# FIT_TCM_P3V3.net
KiCad netlist of a schematic drawn in Altium Designer
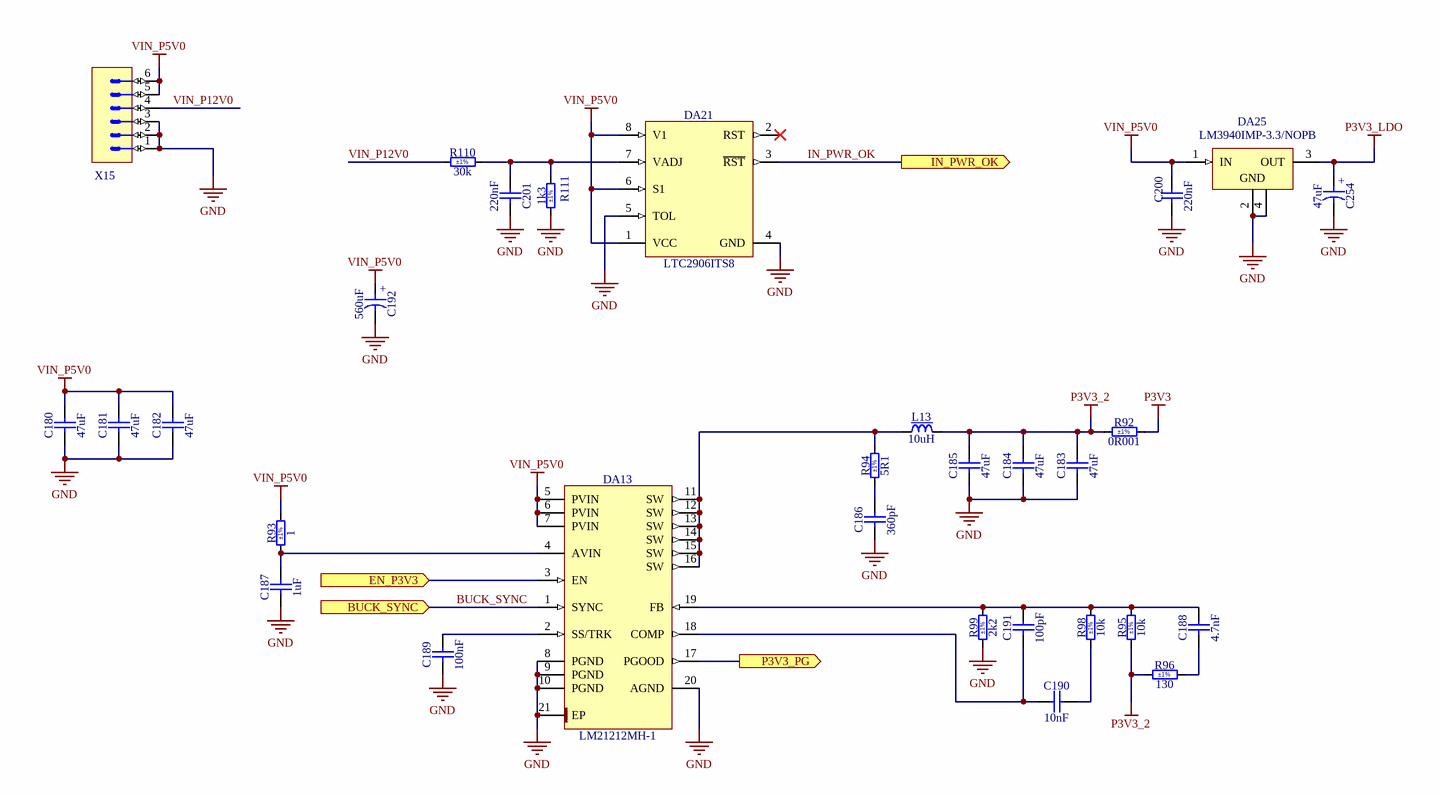
[diagram p0: FIT_TCM_P3V3.SchDoc]

(export (version "E")
  (design (tool "Eeschema 10.0.6"))
  (components
    (comp (ref "C180")
      (value "47uF")
      (footprint "CAPC3225X270N")
      (description "Non-polarised capacitor")
      (fields
        (field (name "PART NUMBER") "CC1210_47UF_16V_20%_X5R")
        (field (name "VOLTAGE") "16V")
        (field (name "AUTHOR") "CERN DEM MR")
      )
      (libsource (lib "Capacitors") (part "Capacitor - non polarized"))
    )
    (comp (ref "C181")
      (value "47uF")
      (footprint "CAPC3225X270N")
      (description "Non-polarised capacitor")
      (fields
        (field (name "PART NUMBER") "CC1210_47UF_16V_20%_X5R")
        (field (name "VOLTAGE") "16V")
        (field (name "AUTHOR") "CERN DEM MR")
      )
      (libsource (lib "Capacitors") (part "Capacitor - non polarized"))
    )
    (comp (ref "C182")
      (value "47uF")
      (footprint "CAPC3225X270N")
      (description "Non-polarised capacitor")
      (fields
        (field (name "PART NUMBER") "CC1210_47UF_16V_20%_X5R")
        (field (name "VOLTAGE") "16V")
        (field (name "AUTHOR") "CERN DEM MR")
      )
      (libsource (lib "Capacitors") (part "Capacitor - non polarized"))
    )
    (comp (ref "C183")
      (value "47uF")
      (footprint "CAPC3225X270N")
      (description "Non-polarised capacitor")
      (fields
        (field (name "PART NUMBER") "CC1210_47UF_16V_20%_X5R")
        (field (name "VOLTAGE") "16V")
        (field (name "AUTHOR") "CERN DEM MR")
      )
      (libsource (lib "Capacitors") (part "Capacitor - non polarized"))
    )
    (comp (ref "C184")
      (value "47uF")
      (footprint "CAPC3225X270N")
      (description "Non-polarised capacitor")
      (fields
        (field (name "PART NUMBER") "CC1210_47UF_16V_20%_X5R")
        (field (name "VOLTAGE") "16V")
        (field (name "AUTHOR") "CERN DEM MR")
      )
      (libsource (lib "Capacitors") (part "Capacitor - non polarized"))
    )
    (comp (ref "C185")
      (value "47uF")
      (footprint "CAPC3225X270N")
      (description "Non-polarised capacitor")
      (fields
        (field (name "PART NUMBER") "CC1210_47UF_16V_20%_X5R")
        (field (name "VOLTAGE") "16V")
        (field (name "AUTHOR") "CERN DEM MR")
      )
      (libsource (lib "Capacitors") (part "Capacitor - non polarized"))
    )
    (comp (ref "C186")
      (value "360pF")
      (footprint "CAPC2013X145N")
      (description "Non-polarised capacitor")
      (fields
        (field (name "PART NUMBER") "CC0805_360PF_50V_5%_C0G")
        (field (name "VOLTAGE") "50V")
        (field (name "AUTHOR") "CERN DEM HF")
      )
      (libsource (lib "Capacitors") (part "Capacitor - non polarized"))
    )
    (comp (ref "C187")
      (value "1uF")
      (footprint "CAPC2012X140N")
      (description "Non-polarised capacitor")
      (fields
        (field (name "PART NUMBER") "CC0805_1UF_25V_10%_X7R")
        (field (name "VOLTAGE") "25V")
        (field (name "AUTHOR") "CERN DEM JLC")
      )
      (libsource (lib "Capacitors") (part "Capacitor - non polarized"))
    )
    (comp (ref "C188")
      (value "4.7nF")
      (footprint "CAPC2012X95N")
      (description "Non-polarised capacitor")
      (fields
        (field (name "PART NUMBER") "CC0805_4.7NF_50V_5%_NP0")
        (field (name "VOLTAGE") "50V")
        (field (name "AUTHOR") "CERN DEM MR")
      )
      (libsource (lib "Capacitors") (part "Capacitor - non polarized"))
    )
    (comp (ref "C189")
      (value "100nF")
      (footprint "CAPC2012X135N")
      (description "Non-polarised capacitor")
      (fields
        (field (name "PART NUMBER") "CC0805_100NF_50V_10%_X7R")
        (field (name "VOLTAGE") "50V")
        (field (name "AUTHOR") "CERN DEM JLC")
      )
      (libsource (lib "Capacitors") (part "Capacitor - non polarized"))
    )
    (comp (ref "C190")
      (value "10nF")
      (footprint "CAPC2012X135N")
      (description "Non-polarised capacitor")
      (fields
        (field (name "PART NUMBER") "CC0805_10NF_50V_10%_X7R")
        (field (name "VOLTAGE") "50V")
        (field (name "AUTHOR") "CERN DEM JLC")
      )
      (libsource (lib "Capacitors") (part "Capacitor - non polarized"))
    )
    (comp (ref "C191")
      (value "100pF")
      (footprint "CAPC2012X135N")
      (description "Non-polarised capacitor")
      (fields
        (field (name "PART NUMBER") "CC0805_100PF_50V_5%_NP0")
        (field (name "VOLTAGE") "50V")
        (field (name "AUTHOR") "CERN DEM JLC")
      )
      (libsource (lib "Capacitors") (part "Capacitor - non polarized"))
    )
    (comp (ref "C192")
      (value "560uF")
      (footprint "CAPAE830X1020N")
      (description "Polarised capacitor")
      (fields
        (field (name "PART NUMBER") "CAE830-1020_560UF_10V_20%")
        (field (name "VOLTAGE") "10V")
        (field (name "AUTHOR") "CERN DEM HF")
      )
      (libsource (lib "Capacitors") (part "Capacitor - polarized"))
    )
    (comp (ref "C200")
      (value "220nF")
      (footprint "CAPC2012X135N")
      (description "Non-polarised capacitor")
      (fields
        (field (name "PART NUMBER") "CC0805_220NF_50V_10%_X7R")
        (field (name "VOLTAGE") "50V")
        (field (name "AUTHOR") "CERN DEM JLC")
      )
      (libsource (lib "Capacitors") (part "Capacitor - non polarized"))
    )
    (comp (ref "C201")
      (value "220nF")
      (footprint "CAPC2012X135N")
      (description "Non-polarised capacitor")
      (fields
        (field (name "PART NUMBER") "CC0805_220NF_50V_10%_X7R")
        (field (name "VOLTAGE") "50V")
        (field (name "AUTHOR") "CERN DEM JLC")
      )
      (libsource (lib "Capacitors") (part "Capacitor - non polarized"))
    )
    (comp (ref "C254")
      (value "47uF")
      (footprint "CAPAE530X610N")
      (description "Polarised capacitor")
      (fields
        (field (name "PART NUMBER") "CAE530-610_47UF_16V_20%")
        (field (name "VOLTAGE") "16V")
        (field (name "AUTHOR") "CERN DEM HF")
      )
      (libsource (lib "Capacitors") (part "Capacitor - polarized"))
    )
    (comp (ref "DA13")
      (value "LM21212MH-1")
      (footprint "TEXAS_PWP0020AA")
      (description "2.95-V To 5.5-V, 12-A, Voltage-Mode Synchronous Buck Regulator with Frequency Synchronization")
      (fields (field (name "MANUFACTURER") "TEXAS INSTRUMENTS") (field (name "AUTHOR") "CERN DEM HF"))
      (libsource (lib "ICs And Semiconductors") (part "LM21212"))
    )
    (comp (ref "DA21")
      (value "LTC2906ITS8")
      (footprint "SOT65P280X100-8N")
      (description "Precision Dual Supply Monitors with One Pin-Selectable Threshold and One Adjustable Input")
      (fields (field (name "MANUFACTURER") "LINEAR TECHNOLOGY") (field (name "AUTHOR") "CERN DEM HF"))
      (libsource (lib "ICs And Semiconductors") (part "LTC2906xTS8"))
    )
    (comp (ref "DA25")
      (value "LM3940IMP-3.3/NOPB")
      (footprint "SOT230P700X180-4N")
      (description "3-Terminal Regulator 1=IN 2=GND 3=OUT 4=GND")
      (fields
        (field (name "MANUFACTURER") "TEXAS INSTRUMENTS")
        (field (name "MANUFACTURER PART NUMBER") "LM3940IMP-3.3")
        (field (name "AUTHOR") "CERN DEM JLC")
      )
      (libsource (lib "ICs And Semiconductors") (part "REG3+1 1IN-2GND-3OUT+4GND"))
    )
    (comp (ref "L13")
      (value "10uH")
      (footprint "IND_VISHAY_IHPL4040DZ-01")
      (description "Inductor With Core")
      (fields
        (field (name "PART NUMBER") "IND4040_10UH_20%_VISHAY_IHLP-4040DZ-01")
        (field (name "POWER") "6.8A")
        (field (name "AUTHOR") "CERN DEM HF")
      )
      (libsource (lib "Inductors & Transformers") (part "Inductor With Magnetic core"))
    )
    (comp (ref "R92")
      (value "0R001")
      (footprint "RESC_BOURNS_CRE2512_0R001-0R004")
      (description "Resistor - 1%")
      (fields
        (field (name "TOLERANCE") "±1%")
        (field (name "PART NUMBER") "R2512_0R001_1%_3W_50PPM_BOURNS_CRE2512")
        (field (name "POWER") "3W")
        (field (name "AUTHOR") "CERN DEM BC")
      )
      (libsource (lib "Resistors") (part "Resistor - 1%"))
    )
    (comp (ref "R93")
      (value "1")
      (footprint "RESC2012X60N")
      (description "Resistor - 1%")
      (fields
        (field (name "TOLERANCE") "±1%")
        (field (name "PART NUMBER") "R0805_1R_1%_0.125W_100PPM")
        (field (name "POWER") "0.125W")
        (field (name "AUTHOR") "CERN DEM HF")
      )
      (libsource (lib "Resistors") (part "Resistor - 1%"))
    )
    (comp (ref "R94")
      (value "5R1")
      (footprint "RESC2012X60N")
      (description "Resistor - 1%")
      (fields
        (field (name "TOLERANCE") "±1%")
        (field (name "PART NUMBER") "R0805_5R1_1%_0.125W_100PPM")
        (field (name "POWER") "0.125W")
        (field (name "AUTHOR") "CERN DEM HF")
      )
      (libsource (lib "Resistors") (part "Resistor - 1%"))
    )
    (comp (ref "R95")
      (value "10k")
      (footprint "RESC2012X60N")
      (description "Resistor - 1%")
      (fields
        (field (name "TOLERANCE") "±1%")
        (field (name "PART NUMBER") "R0805_10K_1%_0.125W_100PPM")
        (field (name "POWER") "0.125W")
        (field (name "AUTHOR") "CERN DEM JLC")
      )
      (libsource (lib "Resistors") (part "Resistor - 1%"))
    )
    (comp (ref "R96")
      (value "130")
      (footprint "RESC2012X60N")
      (description "Resistor - 1%")
      (fields
        (field (name "TOLERANCE") "±1%")
        (field (name "PART NUMBER") "R0805_130R_1%_0.125W_100PPM")
        (field (name "POWER") "0.125W")
        (field (name "AUTHOR") "CERN DEM JLC")
      )
      (libsource (lib "Resistors") (part "Resistor - 1%"))
    )
    (comp (ref "R98")
      (value "10k")
      (footprint "RESC2012X60N")
      (description "Resistor - 1%")
      (fields
        (field (name "TOLERANCE") "±1%")
        (field (name "PART NUMBER") "R0805_10K_1%_0.125W_100PPM")
        (field (name "POWER") "0.125W")
        (field (name "AUTHOR") "CERN DEM JLC")
      )
      (libsource (lib "Resistors") (part "Resistor - 1%"))
    )
    (comp (ref "R99")
      (value "2k2")
      (footprint "RESC2012X60N")
      (description "Resistor - 1%")
      (fields
        (field (name "TOLERANCE") "±1%")
        (field (name "PART NUMBER") "R0805_2K2_1%_0.125W_100PPM")
        (field (name "POWER") "0.125W")
        (field (name "AUTHOR") "CERN DEM JLC")
      )
      (libsource (lib "Resistors") (part "Resistor - 1%"))
    )
    (comp (ref "R110")
      (value "30k")
      (footprint "RESC2012X60N")
      (description "Resistor - 1%")
      (fields
        (field (name "TOLERANCE") "±1%")
        (field (name "PART NUMBER") "R0805_30K_1%_0.125W_100PPM")
        (field (name "POWER") "0.125W")
        (field (name "AUTHOR") "CERN DEM JLC")
      )
      (libsource (lib "Resistors") (part "Resistor - 1%"))
    )
    (comp (ref "R111")
      (value "1k3")
      (footprint "RESC2012X60N")
      (description "Resistor - 1%")
      (fields
        (field (name "TOLERANCE") "±1%")
        (field (name "PART NUMBER") "R0805_1K3_1%_0.125W_100PPM")
        (field (name "POWER") "0.125W")
        (field (name "AUTHOR") "CERN DEM JLC")
      )
      (libsource (lib "Resistors") (part "Resistor - 1%"))
    )
    (comp (ref "X15")
      (value "Mini-Fit BMI")
      (footprint "MOLEX_15-24-9067")
      (description "Connector 6 Male")
      (fields
        (field (name "PART NUMBER") "MOLEX_15-24-9067")
        (field (name "MANUFACTURER") "MOLEX")
        (field (name "AUTHOR") "CERN DEM HF")
      )
      (libsource (lib "Connectors") (part "Connector 6 Male"))
    )
  )
  (nets
    (net (code "1") (name "/BUCK_SYNC") (class "Default")
      (node (ref "DA13") (pin "1") (pinfunction "SYNC_1") (pintype "input"))
    )
    (net (code "2") (name "/EN_P3V3") (class "Default")
      (node (ref "DA13") (pin "3") (pinfunction "EN_3") (pintype "input"))
    )
    (net (code "3") (name "/IN_PWR_OK") (class "Default")
      (node (ref "DA21") (pin "3") (pinfunction "~{RST}_3") (pintype "output"))
    )
    (net (code "4") (name "/P3V3_PG") (class "Default")
      (node (ref "DA13") (pin "17") (pinfunction "PGOOD_17") (pintype "output"))
    )
    (net (code "5") (name "/VIN_P12V0") (class "Default")
      (node (ref "R110") (pin "2") (pinfunction "2_2") (pintype "passive"))
      (node (ref "X15") (pin "4") (pinfunction "4_4") (pintype "bidirectional"))
    )
    (net (code "6") (name "GND") (class "Default")
      (node (ref "C180") (pin "1") (pinfunction "1_1") (pintype "passive"))
      (node (ref "C181") (pin "1") (pinfunction "1_1") (pintype "passive"))
      (node (ref "C182") (pin "1") (pinfunction "1_1") (pintype "passive"))
      (node (ref "C183") (pin "1") (pinfunction "1_1") (pintype "passive"))
      (node (ref "C184") (pin "1") (pinfunction "1_1") (pintype "passive"))
      (node (ref "C185") (pin "1") (pinfunction "1_1") (pintype "passive"))
      (node (ref "C186") (pin "1") (pinfunction "1_1") (pintype "passive"))
      (node (ref "C187") (pin "1") (pinfunction "1_1") (pintype "passive"))
      (node (ref "C189") (pin "1") (pinfunction "1_1") (pintype "passive"))
      (node (ref "C192") (pin "2") (pinfunction "2_2") (pintype "passive"))
      (node (ref "C200") (pin "1") (pinfunction "1_1") (pintype "passive"))
      (node (ref "C201") (pin "1") (pinfunction "1_1") (pintype "passive"))
      (node (ref "C254") (pin "2") (pinfunction "2_2") (pintype "passive"))
      (node (ref "DA13") (pin "10") (pinfunction "PGND_10") (pintype "power_in"))
      (node (ref "DA13") (pin "20") (pinfunction "AGND_20") (pintype "power_in"))
      (node (ref "DA13") (pin "21") (pinfunction "EP_21") (pintype "power_in"))
      (node (ref "DA13") (pin "8") (pinfunction "PGND_8") (pintype "power_in"))
      (node (ref "DA13") (pin "9") (pinfunction "PGND_9") (pintype "power_in"))
      (node (ref "DA21") (pin "4") (pinfunction "GND_4") (pintype "power_in"))
      (node (ref "DA21") (pin "5") (pinfunction "TOL_5") (pintype "input"))
      (node (ref "DA25") (pin "2") (pinfunction "GND_2") (pintype "power_in"))
      (node (ref "DA25") (pin "4") (pinfunction "GND_4") (pintype "power_in"))
      (node (ref "R111") (pin "1") (pinfunction "1_1") (pintype "passive"))
      (node (ref "R99") (pin "1") (pinfunction "1_1") (pintype "passive"))
      (node (ref "X15") (pin "1") (pinfunction "1_1") (pintype "bidirectional"))
      (node (ref "X15") (pin "2") (pinfunction "2_2") (pintype "bidirectional"))
      (node (ref "X15") (pin "3") (pinfunction "3_3") (pintype "bidirectional"))
    )
    (net (code "7") (name "Net-(C186-Pad2)") (class "Default")
      (node (ref "C186") (pin "2") (pinfunction "2_2") (pintype "passive"))
      (node (ref "R94") (pin "1") (pinfunction "1_1") (pintype "passive"))
    )
    (net (code "8") (name "Net-(C188-Pad1)") (class "Default")
      (node (ref "C188") (pin "1") (pinfunction "1_1") (pintype "passive"))
      (node (ref "R96") (pin "1") (pinfunction "1_1") (pintype "passive"))
    )
    (net (code "9") (name "Net-(C190-Pad1)") (class "Default")
      (node (ref "C190") (pin "1") (pinfunction "1_1") (pintype "passive"))
      (node (ref "R98") (pin "1") (pinfunction "1_1") (pintype "passive"))
    )
    (net (code "10") (name "Net-(DA13-AVIN)") (class "Default")
      (node (ref "C187") (pin "2") (pinfunction "2_2") (pintype "passive"))
      (node (ref "DA13") (pin "4") (pinfunction "AVIN_4") (pintype "power_in"))
      (node (ref "R93") (pin "1") (pinfunction "1_1") (pintype "passive"))
    )
    (net (code "11") (name "Net-(DA13-COMP)") (class "Default")
      (node (ref "C190") (pin "2") (pinfunction "2_2") (pintype "passive"))
      (node (ref "C191") (pin "1") (pinfunction "1_1") (pintype "passive"))
      (node (ref "DA13") (pin "18") (pinfunction "COMP_18") (pintype "output"))
    )
    (net (code "12") (name "Net-(DA13-FB)") (class "Default")
      (node (ref "C188") (pin "2") (pinfunction "2_2") (pintype "passive"))
      (node (ref "C191") (pin "2") (pinfunction "2_2") (pintype "passive"))
      (node (ref "DA13") (pin "19") (pinfunction "FB_19") (pintype "input"))
      (node (ref "R95") (pin "2") (pinfunction "2_2") (pintype "passive"))
      (node (ref "R98") (pin "2") (pinfunction "2_2") (pintype "passive"))
      (node (ref "R99") (pin "2") (pinfunction "2_2") (pintype "passive"))
    )
    (net (code "13") (name "Net-(DA13-SS{slash}TRK)") (class "Default")
      (node (ref "C189") (pin "2") (pinfunction "2_2") (pintype "passive"))
      (node (ref "DA13") (pin "2") (pinfunction "SS/TRK_2") (pintype "input"))
    )
    (net (code "14") (name "Net-(DA13-SW-Pad11)") (class "Default")
      (node (ref "DA13") (pin "11") (pinfunction "SW_11") (pintype "output"))
      (node (ref "DA13") (pin "12") (pinfunction "SW_12") (pintype "output"))
      (node (ref "DA13") (pin "13") (pinfunction "SW_13") (pintype "output"))
      (node (ref "DA13") (pin "14") (pinfunction "SW_14") (pintype "output"))
      (node (ref "DA13") (pin "15") (pinfunction "SW_15") (pintype "output"))
      (node (ref "DA13") (pin "16") (pinfunction "SW_16") (pintype "output"))
      (node (ref "L13") (pin "1") (pinfunction "1_1") (pintype "passive"))
      (node (ref "R94") (pin "2") (pinfunction "2_2") (pintype "passive"))
    )
    (net (code "15") (name "Net-(DA21-VADJ)") (class "Default")
      (node (ref "C201") (pin "2") (pinfunction "2_2") (pintype "passive"))
      (node (ref "DA21") (pin "7") (pinfunction "VADJ_7") (pintype "input"))
      (node (ref "R110") (pin "1") (pinfunction "1_1") (pintype "passive"))
      (node (ref "R111") (pin "2") (pinfunction "2_2") (pintype "passive"))
    )
    (net (code "16") (name "P3V3") (class "Default")
      (node (ref "R92") (pin "2") (pinfunction "2_2") (pintype "passive"))
    )
    (net (code "17") (name "P3V3_2") (class "Default")
      (node (ref "C183") (pin "2") (pinfunction "2_2") (pintype "passive"))
      (node (ref "C184") (pin "2") (pinfunction "2_2") (pintype "passive"))
      (node (ref "C185") (pin "2") (pinfunction "2_2") (pintype "passive"))
      (node (ref "L13") (pin "2") (pinfunction "2_2") (pintype "passive"))
      (node (ref "R92") (pin "1") (pinfunction "1_1") (pintype "passive"))
      (node (ref "R95") (pin "1") (pinfunction "1_1") (pintype "passive"))
      (node (ref "R96") (pin "2") (pinfunction "2_2") (pintype "passive"))
    )
    (net (code "18") (name "P3V3_LDO") (class "Default")
      (node (ref "C254") (pin "1") (pinfunction "1_1") (pintype "passive"))
      (node (ref "DA25") (pin "3") (pinfunction "OUT_3") (pintype "power_in"))
    )
    (net (code "19") (name "VIN_P5V0") (class "Default")
      (node (ref "C180") (pin "2") (pinfunction "2_2") (pintype "passive"))
      (node (ref "C181") (pin "2") (pinfunction "2_2") (pintype "passive"))
      (node (ref "C182") (pin "2") (pinfunction "2_2") (pintype "passive"))
      (node (ref "C192") (pin "1") (pinfunction "1_1") (pintype "passive"))
      (node (ref "C200") (pin "2") (pinfunction "2_2") (pintype "passive"))
      (node (ref "DA13") (pin "5") (pinfunction "PVIN_5") (pintype "power_in"))
      (node (ref "DA13") (pin "6") (pinfunction "PVIN_6") (pintype "power_in"))
      (node (ref "DA13") (pin "7") (pinfunction "PVIN_7") (pintype "power_in"))
      (node (ref "DA21") (pin "1") (pinfunction "VCC_1") (pintype "power_in"))
      (node (ref "DA21") (pin "6") (pinfunction "S1_6") (pintype "input"))
      (node (ref "DA21") (pin "8") (pinfunction "V1_8") (pintype "input"))
      (node (ref "DA25") (pin "1") (pinfunction "IN_1") (pintype "input"))
      (node (ref "R93") (pin "2") (pinfunction "2_2") (pintype "passive"))
      (node (ref "X15") (pin "5") (pinfunction "5_5") (pintype "bidirectional"))
      (node (ref "X15") (pin "6") (pinfunction "6_6") (pintype "bidirectional"))
    )
    (net (code "20") (name "unconnected-(DA21-RST-Pad2)") (class "Default")
      (node (ref "DA21") (pin "2") (pinfunction "RST_2") (pintype "output+no_connect"))
    )
  )
)
